# SonoffIR.net
KiCad netlist of a schematic drawn in EAGLE
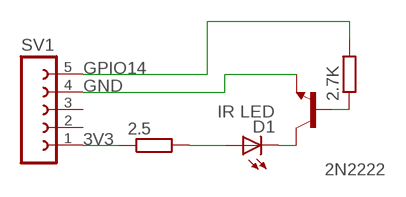
[diagram p0: schematic, sheet 1]

(export (version "E")
  (design (tool "Eeschema 10.0.6"))
  (components
    (comp (ref "2.5")
      (value "R-EU_0204/2V")
      (footprint "eagle-import:0204V")
      (libsource (lib "eagle-import") (part "R-EU_0204/2V"))
    )
    (comp (ref "2.7K")
      (value "R-EU_0204/2V")
      (footprint "eagle-import:0204V")
      (libsource (lib "eagle-import") (part "R-EU_0204/2V"))
    )
    (comp (ref "2N2222")
      (value "2N3565")
      (footprint "eagle-import:TO92")
      (libsource (lib "eagle-import") (part "2N3565"))
    )
    (comp (ref "D1")
      (value "IR LED")
      (footprint "eagle-import:SFH482")
      (libsource (lib "eagle-import") (part "SFH482"))
    )
    (comp (ref "SV1")
      (value "FE05-1")
      (footprint "eagle-import:FE05-1")
      (libsource (lib "eagle-import") (part "FE05-1"))
    )
  )
  (nets
    (net (code "1") (name "/3V3") (class "Default")
      (node (ref "2.5") (pin "1") (pinfunction "1_1") (pintype "passive"))
      (node (ref "SV1") (pin "1") (pinfunction "1_1") (pintype "passive"))
    )
    (net (code "2") (name "/GND") (class "Default")
      (node (ref "2N2222") (pin "3") (pinfunction "E_3") (pintype "passive"))
      (node (ref "SV1") (pin "4") (pinfunction "4_4") (pintype "passive"))
    )
    (net (code "3") (name "/GPIO14") (class "Default")
      (node (ref "2.7K") (pin "2") (pinfunction "2_2") (pintype "passive"))
      (node (ref "SV1") (pin "5") (pinfunction "5_5") (pintype "passive"))
    )
    (net (code "4") (name "Net-(2.5-Pad2)") (class "Default")
      (node (ref "2.5") (pin "2") (pinfunction "2_2") (pintype "passive"))
      (node (ref "D1") (pin "A") (pinfunction "A_A") (pintype "passive"))
    )
    (net (code "5") (name "Net-(2N2222-B)") (class "Default")
      (node (ref "2.7K") (pin "1") (pinfunction "1_1") (pintype "passive"))
      (node (ref "2N2222") (pin "2") (pinfunction "B_2") (pintype "passive"))
    )
    (net (code "6") (name "Net-(2N2222-C)") (class "Default")
      (node (ref "2N2222") (pin "1") (pinfunction "C_1") (pintype "passive"))
      (node (ref "D1") (pin "K") (pinfunction "C_K") (pintype "passive"))
    )
    (net (code "7") (name "unconnected-(SV1-Pad2)") (class "Default")
      (node (ref "SV1") (pin "2") (pinfunction "2_2") (pintype "passive"))
    )
    (net (code "8") (name "unconnected-(SV1-Pad3)") (class "Default")
      (node (ref "SV1") (pin "3") (pinfunction "3_3") (pintype "passive"))
    )
  )
)
